# utilidong-septic-sepic-lt1610-mk-1_2.net
KiCad netlist of a schematic drawn in EAGLE
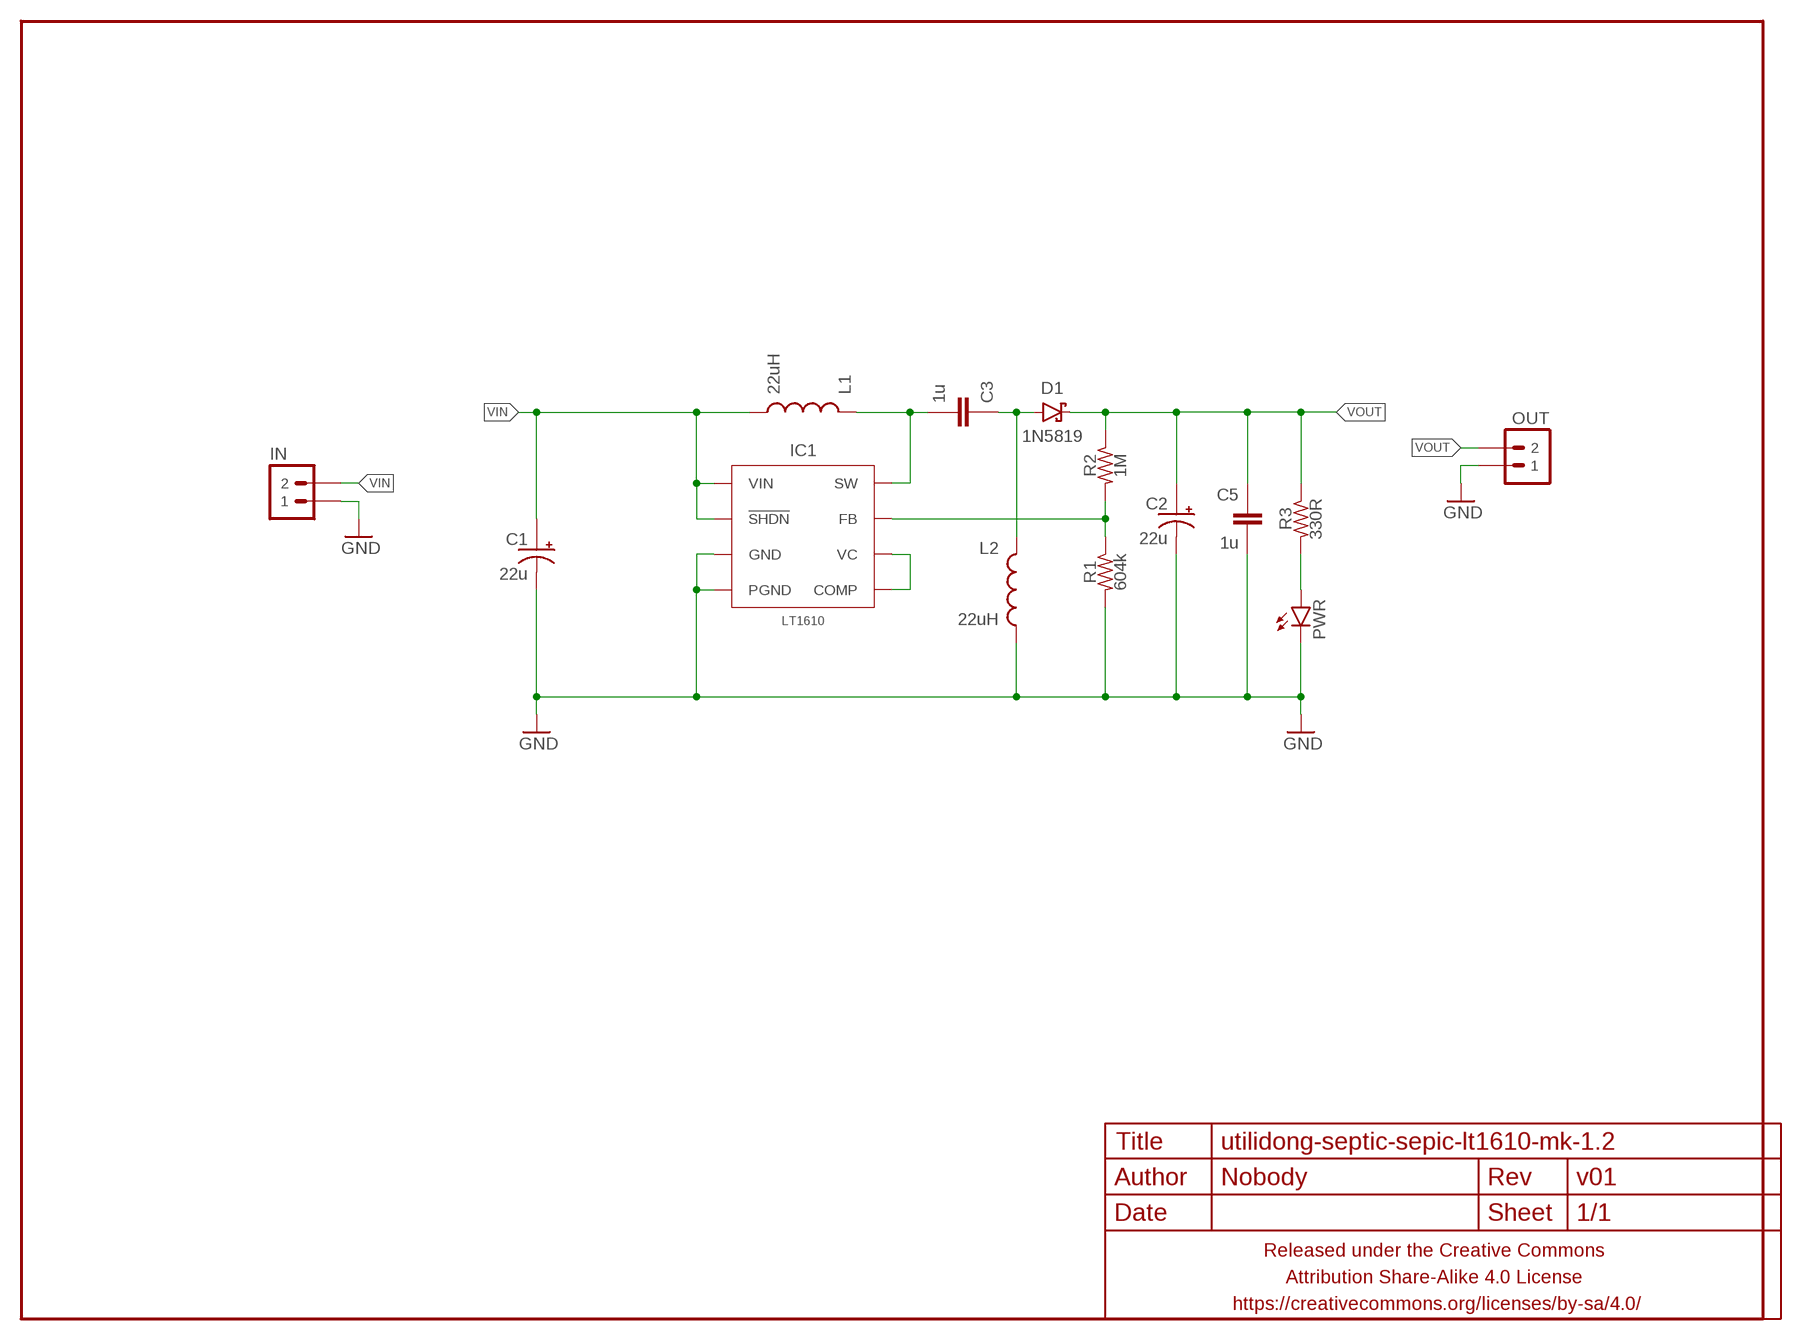
[diagram p0: schematic, sheet 1]

(export (version "E")
  (design (tool "Eeschema 10.0.6"))
  (components
    (comp (ref "C1")
      (value "22u")
      (footprint "eagle-import:E2,5-6")
      (libsource (lib "eagle-import") (part "CAPACITOR-POLARIZEDE2.5-6"))
    )
    (comp (ref "C2")
      (value "22u")
      (footprint "eagle-import:E2,5-6")
      (libsource (lib "eagle-import") (part "CAPACITOR-POLARIZEDE2.5-6"))
    )
    (comp (ref "C3")
      (value "1u")
      (footprint "eagle-import:C025-024X044")
      (libsource (lib "eagle-import") (part "CAPACITOR-CERAMIC025-024X044"))
    )
    (comp (ref "C5")
      (value "1u")
      (footprint "eagle-import:C025-024X044")
      (libsource (lib "eagle-import") (part "CAPACITOR-CERAMIC025-024X044"))
    )
    (comp (ref "D1")
      (value "1N5819")
      (footprint "eagle-import:DIODE-7.62MM")
      (libsource (lib "eagle-import") (part "DIODE-SCHOTTKYPTH-7.62MM"))
    )
    (comp (ref "FRAME1")
      (value "FRAME-LETTERNO_PACKAGE")
      (footprint "eagle-import:DUMMY")
      (fields (field (name "DESIGNER") "Nobody"))
      (libsource (lib "eagle-import") (part "FRAME-LETTERNO_PACKAGE"))
    )
    (comp (ref "IC1")
      (value "LT1610")
      (footprint "eagle-import:SO08")
      (libsource (lib "eagle-import") (part "LT1610SOICN8"))
    )
    (comp (ref "IN")
      (value "M02PTH-CENTERED-R+")
      (footprint "eagle-import:1X02-CENTER-R+")
      (libsource (lib "eagle-import") (part "M02PTH-CENTERED-R+"))
    )
    (comp (ref "L1")
      (value "22uH")
      (footprint "eagle-import:MURATA-1100R")
      (libsource (lib "eagle-import") (part "INDUCTORMURATA-1100R"))
    )
    (comp (ref "L2")
      (value "22uH")
      (footprint "eagle-import:MURATA-1100R")
      (libsource (lib "eagle-import") (part "INDUCTORMURATA-1100R"))
    )
    (comp (ref "OUT")
      (value "M02PTH-CENTERED-R+")
      (footprint "eagle-import:1X02-CENTER-R+")
      (libsource (lib "eagle-import") (part "M02PTH-CENTERED-R+"))
    )
    (comp (ref "PWR")
      (value "LED3MM-LESS")
      (footprint "eagle-import:LED3MM-LESSSILK")
      (libsource (lib "eagle-import") (part "LED3MM-LESS"))
    )
    (comp (ref "R1")
      (value "604k")
      (footprint "eagle-import:RESISTOR-AXIAL-PTH-5.08MM")
      (libsource (lib "eagle-import") (part "RESISTORPTH-AXIAL-5.08MM"))
    )
    (comp (ref "R2")
      (value "1M")
      (footprint "eagle-import:RESISTOR-AXIAL-PTH-5.08MM")
      (libsource (lib "eagle-import") (part "RESISTORPTH-AXIAL-5.08MM"))
    )
    (comp (ref "R3")
      (value "330R")
      (footprint "eagle-import:RESISTOR-AXIAL-PTH-5.08MM")
      (libsource (lib "eagle-import") (part "RESISTORPTH-AXIAL-5.08MM"))
    )
  )
  (nets
    (net (code "1") (name "GND") (class "Default")
      (node (ref "C1") (pin "-") (pinfunction "-_-") (pintype "passive"))
      (node (ref "C2") (pin "-") (pinfunction "-_-") (pintype "passive"))
      (node (ref "C5") (pin "2") (pinfunction "2_2") (pintype "passive"))
      (node (ref "IC1") (pin "4") (pinfunction "PGND_4") (pintype "passive"))
      (node (ref "IC1") (pin "7") (pinfunction "GND_7") (pintype "passive"))
      (node (ref "IN") (pin "1") (pinfunction "1_1") (pintype "passive"))
      (node (ref "L2") (pin "P$2") (pinfunction "2_P$2") (pintype "passive"))
      (node (ref "OUT") (pin "1") (pinfunction "1_1") (pintype "passive"))
      (node (ref "PWR") (pin "K") (pinfunction "C_K") (pintype "passive"))
      (node (ref "R1") (pin "P$2") (pinfunction "2_P$2") (pintype "passive"))
    )
    (net (code "2") (name "Net-(IC1-COMP)") (class "Default")
      (node (ref "IC1") (pin "1") (pinfunction "VC_1") (pintype "passive"))
      (node (ref "IC1") (pin "8") (pinfunction "COMP_8") (pintype "passive"))
    )
    (net (code "3") (name "Net-(IC1-FB)") (class "Default")
      (node (ref "IC1") (pin "2") (pinfunction "FB_2") (pintype "passive"))
      (node (ref "R1") (pin "P$1") (pinfunction "1_P$1") (pintype "passive"))
      (node (ref "R2") (pin "P$2") (pinfunction "2_P$2") (pintype "passive"))
    )
    (net (code "4") (name "Net-(IC1-SW)") (class "Default")
      (node (ref "C3") (pin "2") (pinfunction "2_2") (pintype "passive"))
      (node (ref "IC1") (pin "5") (pinfunction "SW_5") (pintype "passive"))
      (node (ref "L1") (pin "P$1") (pinfunction "1_P$1") (pintype "passive"))
    )
    (net (code "5") (name "Net-(L2-1)") (class "Default")
      (node (ref "C3") (pin "1") (pinfunction "1_1") (pintype "passive"))
      (node (ref "D1") (pin "A") (pinfunction "A_A") (pintype "passive"))
      (node (ref "L2") (pin "P$1") (pinfunction "1_P$1") (pintype "passive"))
    )
    (net (code "6") (name "Net-(R3-2)") (class "Default")
      (node (ref "PWR") (pin "A") (pinfunction "A_A") (pintype "passive"))
      (node (ref "R3") (pin "P$2") (pinfunction "2_P$2") (pintype "passive"))
    )
    (net (code "7") (name "VIN") (class "Default")
      (node (ref "C1") (pin "+") (pinfunction "+_+") (pintype "passive"))
      (node (ref "IC1") (pin "3") (pinfunction "~{SHDN}_3") (pintype "passive"))
      (node (ref "IC1") (pin "6") (pinfunction "VIN_6") (pintype "passive"))
      (node (ref "IN") (pin "2") (pinfunction "2_2") (pintype "passive"))
      (node (ref "L1") (pin "P$2") (pinfunction "2_P$2") (pintype "passive"))
    )
    (net (code "8") (name "VOUT") (class "Default")
      (node (ref "C2") (pin "+") (pinfunction "+_+") (pintype "passive"))
      (node (ref "C5") (pin "1") (pinfunction "1_1") (pintype "passive"))
      (node (ref "D1") (pin "K") (pinfunction "C_K") (pintype "passive"))
      (node (ref "OUT") (pin "2") (pinfunction "2_2") (pintype "passive"))
      (node (ref "R2") (pin "P$1") (pinfunction "1_P$1") (pintype "passive"))
      (node (ref "R3") (pin "P$1") (pinfunction "1_P$1") (pintype "passive"))
    )
  )
)
